# SCH_shield_test_2024-01-13.net
KiCad netlist of a schematic drawn in EasyEDA
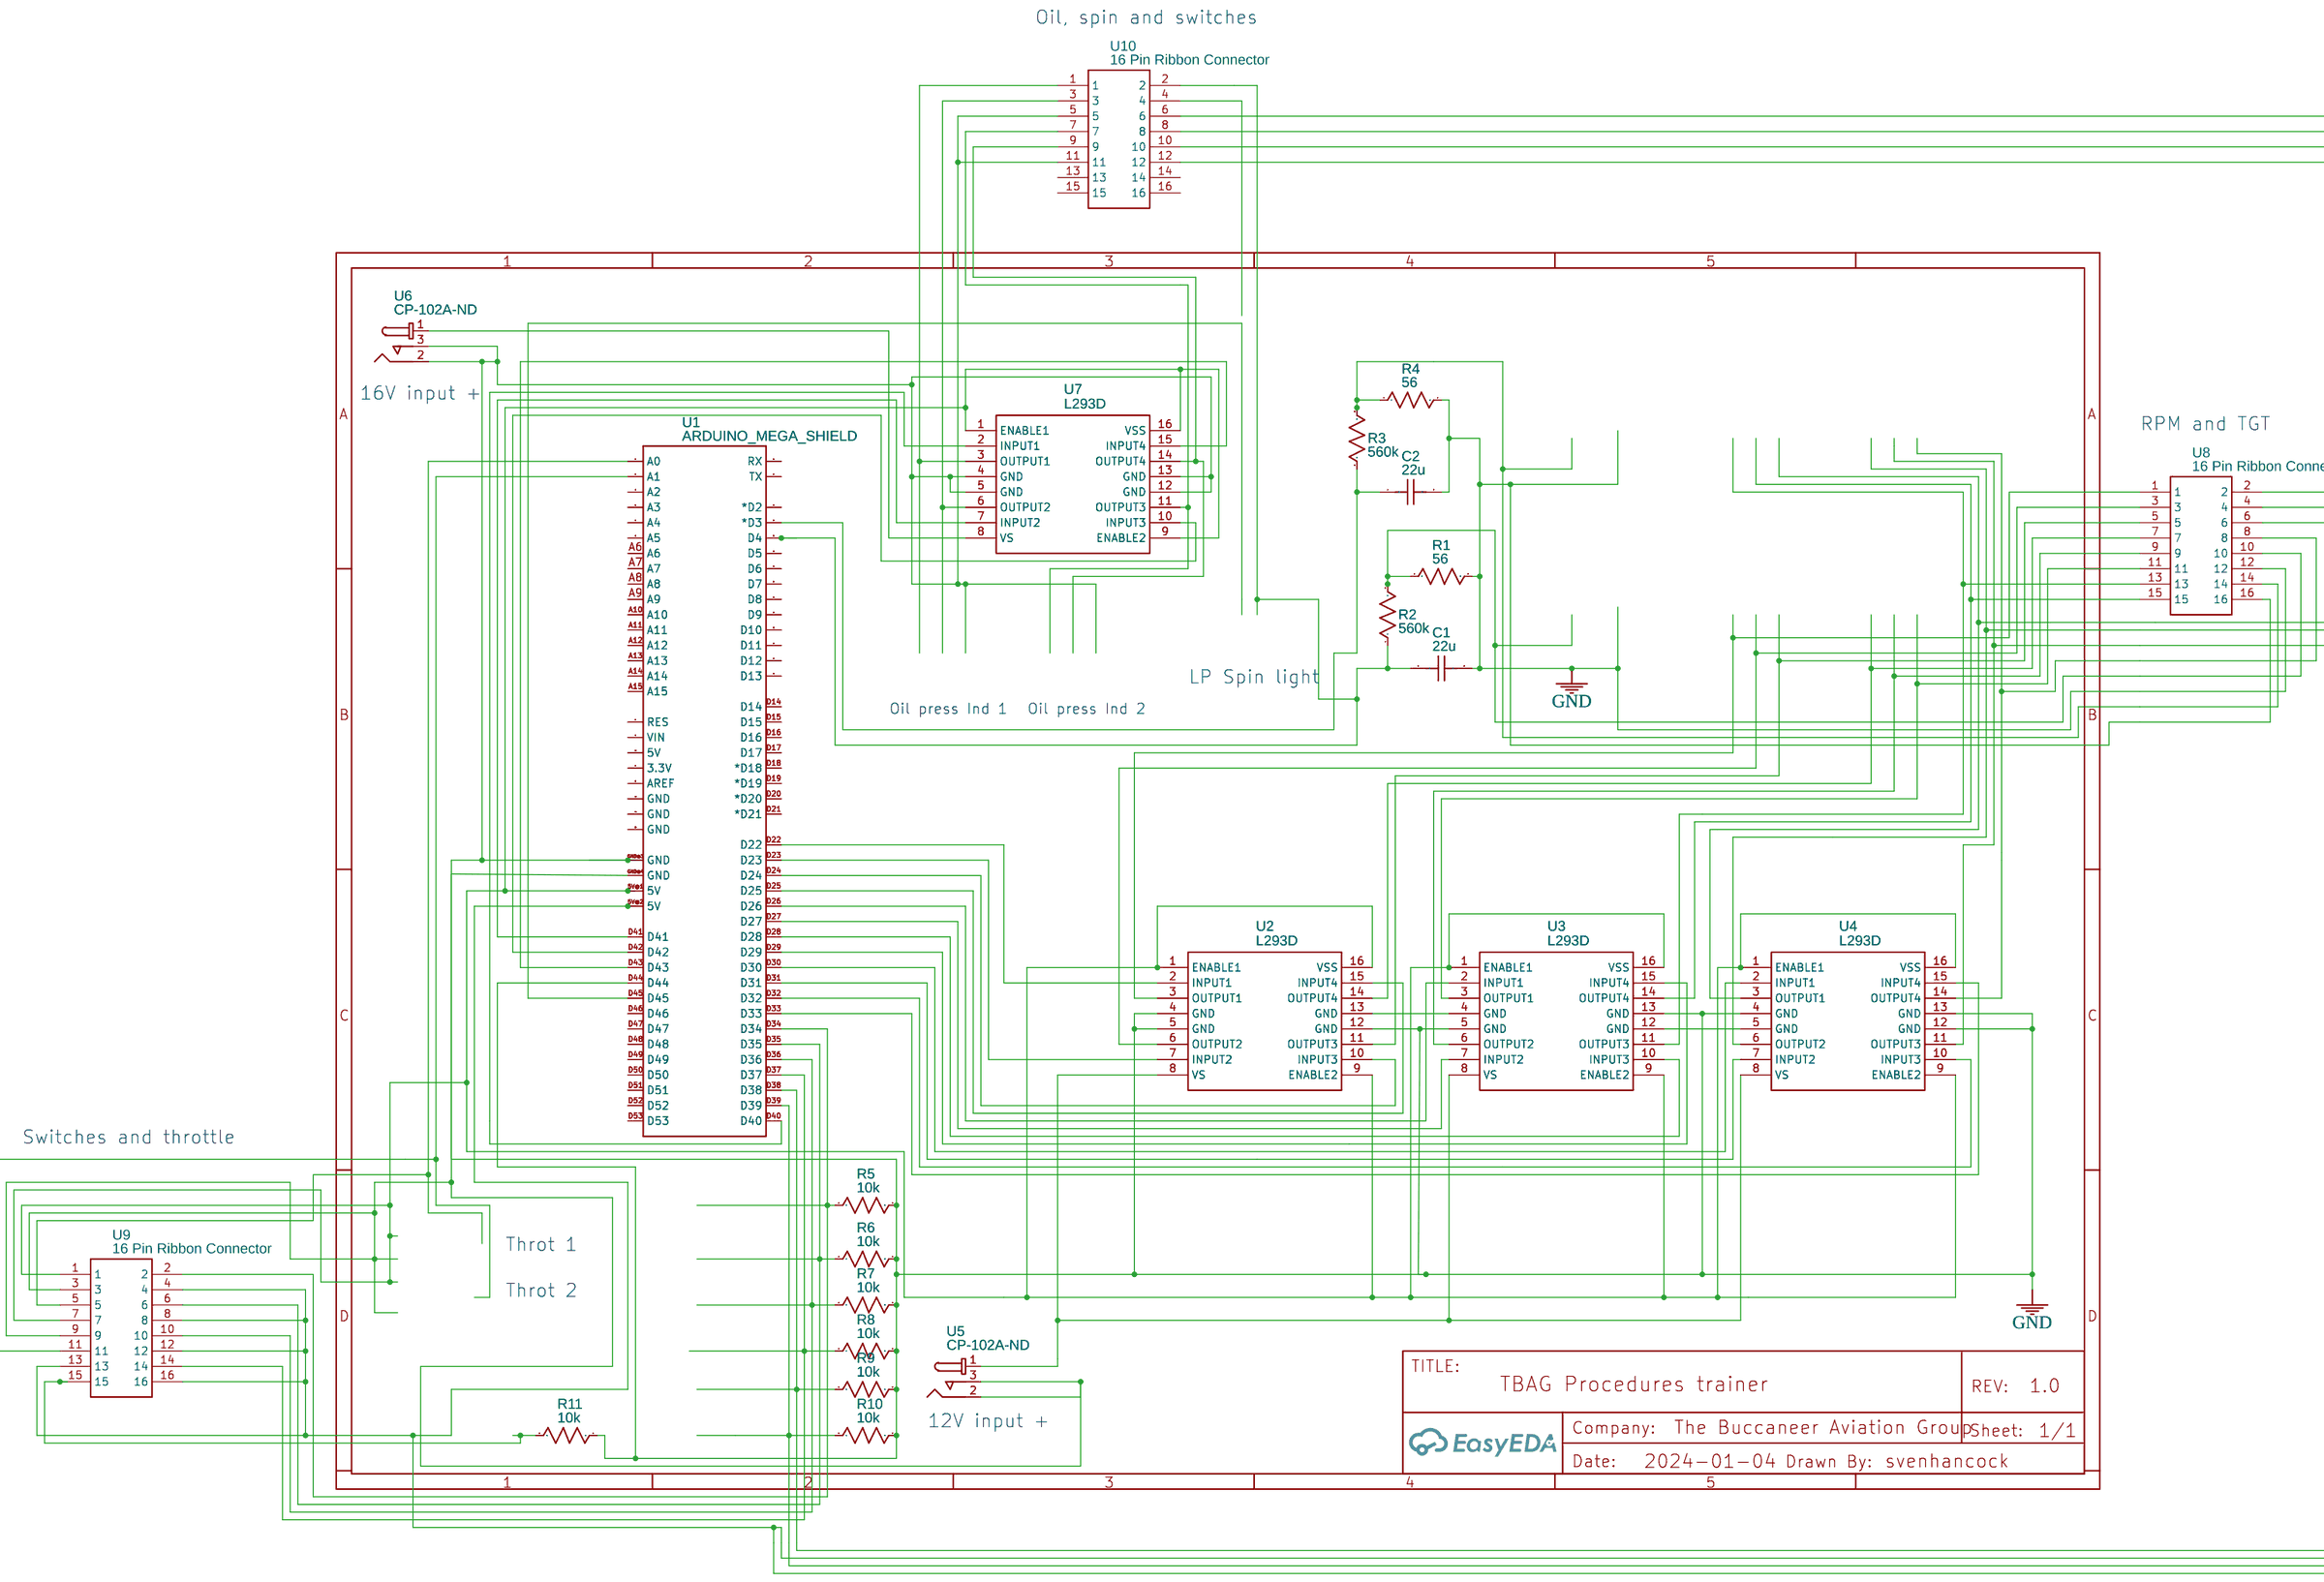
[diagram p0: schematic sheet]

(export (version "E")
  (design (tool "Eeschema 10.0.6"))
  (components
    (comp (ref "C1") (value "22u") (libsource (lib "") (part "C_0603_US")))
    (comp (ref "C2") (value "22u") (libsource (lib "") (part "C_0603_US")))
    (comp (ref "R1") (value "56") (libsource (lib "") (part "R_0603_US")))
    (comp (ref "R2") (value "560k") (libsource (lib "") (part "R_0603_US_1")))
    (comp (ref "R3") (value "560k") (libsource (lib "") (part "R_0603_US_1")))
    (comp (ref "R4") (value "56") (libsource (lib "") (part "R_0603_US")))
    (comp (ref "R5") (value "10k") (libsource (lib "") (part "R_0603_US")))
    (comp (ref "R6") (value "10k") (libsource (lib "") (part "R_0603_US")))
    (comp (ref "R7") (value "10k") (libsource (lib "") (part "R_0603_US")))
    (comp (ref "R8") (value "10k") (libsource (lib "") (part "R_0603_US")))
    (comp (ref "R9") (value "10k") (libsource (lib "") (part "R_0603_US")))
    (comp (ref "R10") (value "10k") (libsource (lib "") (part "R_0603_US")))
    (comp (ref "R11") (value "10k") (libsource (lib "") (part "R_0603_US")))
    (comp (ref "U1") (value "ARDUINO_MEGA_SHIELD") (libsource (lib "") (part "ARDUINO_MEGA_SHIELD")))
    (comp (ref "U2")
      (value "L293D")
      (fields (field (name "Manufacturer") "ST(意法半导体)"))
      (libsource (lib "") (part "L293D"))
    )
    (comp (ref "U3")
      (value "L293D")
      (fields (field (name "Manufacturer") "ST(意法半导体)"))
      (libsource (lib "") (part "L293D"))
    )
    (comp (ref "U4")
      (value "L293D")
      (fields (field (name "Manufacturer") "ST(意法半导体)"))
      (libsource (lib "") (part "L293D"))
    )
    (comp (ref "U5") (value "CP-102A-ND") (libsource (lib "") (part "CP-102A-ND")))
    (comp (ref "U6") (value "CP-102A-ND") (libsource (lib "") (part "CP-102A-ND")))
    (comp (ref "U7")
      (value "L293D")
      (fields (field (name "Manufacturer") "ST(意法半导体)"))
      (libsource (lib "") (part "L293D"))
    )
    (comp (ref "U8") (value "16 Pin Ribbon Connector") (libsource (lib "") (part "16 Pin Ribbon Connector")))
    (comp (ref "U9") (value "16 Pin Ribbon Connector") (libsource (lib "") (part "16 Pin Ribbon Connector")))
    (comp (ref "U10") (value "16 Pin Ribbon Connector") (libsource (lib "") (part "16 Pin Ribbon Connector")))
  )
  (nets
    (net (code "1") (name "GND") (class "Default")
      (node (ref "C1") (pin "2") (pinfunction "2_2") (pintype "unspecified"))
      (node (ref "C2") (pin "2") (pinfunction "2_2") (pintype "unspecified"))
      (node (ref "R1") (pin "2") (pinfunction "2_2") (pintype "unspecified"))
      (node (ref "R10") (pin "2") (pinfunction "2_2") (pintype "unspecified"))
      (node (ref "R11") (pin "2") (pinfunction "2_2") (pintype "unspecified"))
      (node (ref "R4") (pin "2") (pinfunction "2_2") (pintype "unspecified"))
      (node (ref "R5") (pin "2") (pinfunction "2_2") (pintype "unspecified"))
      (node (ref "R6") (pin "2") (pinfunction "2_2") (pintype "unspecified"))
      (node (ref "R7") (pin "2") (pinfunction "2_2") (pintype "unspecified"))
      (node (ref "R8") (pin "2") (pinfunction "2_2") (pintype "unspecified"))
      (node (ref "R9") (pin "2") (pinfunction "2_2") (pintype "unspecified"))
      (node (ref "U1") (pin "D44") (pinfunction "D44_D44") (pintype "unspecified"))
      (node (ref "U1") (pin "GND@3") (pinfunction "GND_GND@3") (pintype "unspecified"))
      (node (ref "U10") (pin "11") (pinfunction "11_11") (pintype "unspecified"))
      (node (ref "U10") (pin "5") (pinfunction "5_5") (pintype "unspecified"))
      (node (ref "U2") (pin "12") (pinfunction "GND_12") (pintype "unspecified"))
      (node (ref "U2") (pin "4") (pinfunction "GND_4") (pintype "unspecified"))
      (node (ref "U2") (pin "5") (pinfunction "GND_5") (pintype "unspecified"))
      (node (ref "U3") (pin "13") (pinfunction "GND_13") (pintype "unspecified"))
      (node (ref "U3") (pin "5") (pinfunction "GND_5") (pintype "unspecified"))
      (node (ref "U4") (pin "12") (pinfunction "GND_12") (pintype "unspecified"))
      (node (ref "U4") (pin "13") (pinfunction "GND_13") (pintype "unspecified"))
      (node (ref "U4") (pin "4") (pinfunction "GND_4") (pintype "unspecified"))
      (node (ref "U6") (pin "2") (pintype "unspecified"))
      (node (ref "U6") (pin "3") (pintype "unspecified"))
      (node (ref "U7") (pin "12") (pinfunction "GND_12") (pintype "unspecified"))
      (node (ref "U7") (pin "13") (pinfunction "GND_13") (pintype "unspecified"))
      (node (ref "U7") (pin "4") (pinfunction "GND_4") (pintype "unspecified"))
      (node (ref "U7") (pin "5") (pinfunction "GND_5") (pintype "unspecified"))
      (node (ref "U8") (pin "12") (pinfunction "12_12") (pintype "unspecified"))
      (node (ref "U8") (pin "16") (pinfunction "16_16") (pintype "unspecified"))
    )
    (net (code "2") (name "Net-(C1-Pad1)") (class "Default")
      (node (ref "C1") (pin "1") (pinfunction "1_1") (pintype "unspecified"))
      (node (ref "R2") (pin "1") (pinfunction "1_1") (pintype "unspecified"))
      (node (ref "U1") (pin "D4") (pinfunction "D4_D4") (pintype "unspecified"))
      (node (ref "U10") (pin "2") (pinfunction "2_2") (pintype "unspecified"))
    )
    (net (code "3") (name "Net-(R1-Pad1)") (class "Default")
      (node (ref "R1") (pin "1") (pinfunction "1_1") (pintype "unspecified"))
      (node (ref "R2") (pin "2") (pinfunction "2_2") (pintype "unspecified"))
      (node (ref "U8") (pin "10") (pinfunction "10_10") (pintype "unspecified"))
    )
    (net (code "4") (name "Net-(R3-Pad2)") (class "Default")
      (node (ref "R3") (pin "2") (pinfunction "2_2") (pintype "unspecified"))
      (node (ref "R4") (pin "1") (pinfunction "1_1") (pintype "unspecified"))
      (node (ref "U8") (pin "14") (pinfunction "14_14") (pintype "unspecified"))
    )
    (net (code "5") (name "Net-(R5-Pad1)") (class "Default")
      (node (ref "R5") (pin "1") (pinfunction "1_1") (pintype "unspecified"))
      (node (ref "U1") (pin "D34") (pinfunction "D34_D34") (pintype "unspecified"))
      (node (ref "U9") (pin "2") (pinfunction "2_2") (pintype "unspecified"))
    )
    (net (code "6") (name "Net-(R6-Pad1)") (class "Default")
      (node (ref "R6") (pin "1") (pinfunction "1_1") (pintype "unspecified"))
      (node (ref "U1") (pin "D35") (pinfunction "D35_D35") (pintype "unspecified"))
      (node (ref "U9") (pin "6") (pinfunction "6_6") (pintype "unspecified"))
    )
    (net (code "7") (name "Net-(R7-Pad1)") (class "Default")
      (node (ref "R7") (pin "1") (pinfunction "1_1") (pintype "unspecified"))
      (node (ref "U1") (pin "D36") (pinfunction "D36_D36") (pintype "unspecified"))
      (node (ref "U9") (pin "10") (pinfunction "10_10") (pintype "unspecified"))
    )
    (net (code "8") (name "Net-(R8-Pad1)") (class "Default")
      (node (ref "R8") (pin "1") (pinfunction "1_1") (pintype "unspecified"))
      (node (ref "U1") (pin "D37") (pinfunction "D37_D37") (pintype "unspecified"))
      (node (ref "U9") (pin "14") (pinfunction "14_14") (pintype "unspecified"))
    )
    (net (code "9") (name "Net-(R9-Pad1)") (class "Default")
      (node (ref "R9") (pin "1") (pinfunction "1_1") (pintype "unspecified"))
      (node (ref "U1") (pin "D38") (pinfunction "D38_D38") (pintype "unspecified"))
      (node (ref "U10") (pin "6") (pinfunction "6_6") (pintype "unspecified"))
    )
    (net (code "10") (name "Net-(R10-Pad1)") (class "Default")
      (node (ref "R10") (pin "1") (pinfunction "1_1") (pintype "unspecified"))
      (node (ref "U1") (pin "D39") (pinfunction "D39_D39") (pintype "unspecified"))
      (node (ref "U10") (pin "10") (pinfunction "10_10") (pintype "unspecified"))
    )
    (net (code "11") (name "Net-(R11-Pad1)") (class "Default")
      (node (ref "R11") (pin "1") (pinfunction "1_1") (pintype "unspecified"))
      (node (ref "U9") (pin "15") (pinfunction "15_15") (pintype "unspecified"))
    )
    (net (code "12") (name "Net-(U1-*D3)") (class "Default")
      (node (ref "C2") (pin "1") (pinfunction "1_1") (pintype "unspecified"))
      (node (ref "R3") (pin "1") (pinfunction "1_1") (pintype "unspecified"))
      (node (ref "U1") (pin "D3") (pinfunction "*D3_D3") (pintype "unspecified"))
    )
    (net (code "13") (name "Net-(U1-5V-Pad5V@2)") (class "Default")
      (node (ref "U1") (pin "5V@2") (pinfunction "5V_5V@2") (pintype "unspecified"))
      (node (ref "U10") (pin "12") (pinfunction "12_12") (pintype "unspecified"))
      (node (ref "U10") (pin "8") (pinfunction "8_8") (pintype "unspecified"))
      (node (ref "U9") (pin "12") (pinfunction "12_12") (pintype "unspecified"))
      (node (ref "U9") (pin "13") (pinfunction "13_13") (pintype "unspecified"))
      (node (ref "U9") (pin "16") (pinfunction "16_16") (pintype "unspecified"))
      (node (ref "U9") (pin "4") (pinfunction "4_4") (pintype "unspecified"))
      (node (ref "U9") (pin "8") (pinfunction "8_8") (pintype "unspecified"))
    )
    (net (code "14") (name "Net-(U1-PadA0)") (class "Default")
      (node (ref "U1") (pin "A0") (pinfunction "A0_A0") (pintype "unspecified"))
      (node (ref "U9") (pin "5") (pinfunction "5_5") (pintype "unspecified"))
    )
    (net (code "15") (name "Net-(U1-PadA1)") (class "Default")
      (node (ref "U1") (pin "A1") (pinfunction "A1_A1") (pintype "unspecified"))
      (node (ref "U9") (pin "11") (pinfunction "11_11") (pintype "unspecified"))
    )
    (net (code "16") (name "Net-(U2-ENABLE1)") (class "Default")
      (node (ref "U1") (pin "5V@1") (pinfunction "5V_5V@1") (pintype "unspecified"))
      (node (ref "U2") (pin "1") (pinfunction "ENABLE1_1") (pintype "unspecified"))
      (node (ref "U2") (pin "16") (pinfunction "VSS_16") (pintype "unspecified"))
      (node (ref "U2") (pin "9") (pinfunction "ENABLE2_9") (pintype "unspecified"))
      (node (ref "U3") (pin "1") (pinfunction "ENABLE1_1") (pintype "unspecified"))
      (node (ref "U3") (pin "16") (pinfunction "VSS_16") (pintype "unspecified"))
      (node (ref "U3") (pin "9") (pinfunction "ENABLE2_9") (pintype "unspecified"))
      (node (ref "U4") (pin "1") (pinfunction "ENABLE1_1") (pintype "unspecified"))
      (node (ref "U4") (pin "16") (pinfunction "VSS_16") (pintype "unspecified"))
      (node (ref "U4") (pin "9") (pinfunction "ENABLE2_9") (pintype "unspecified"))
      (node (ref "U7") (pin "1") (pinfunction "ENABLE1_1") (pintype "unspecified"))
      (node (ref "U7") (pin "16") (pinfunction "VSS_16") (pintype "unspecified"))
      (node (ref "U7") (pin "9") (pinfunction "ENABLE2_9") (pintype "unspecified"))
      (node (ref "U9") (pin "1") (pinfunction "1_1") (pintype "unspecified"))
      (node (ref "U9") (pin "7") (pinfunction "7_7") (pintype "unspecified"))
    )
    (net (code "17") (name "Net-(U2-GND-Pad13)") (class "Default")
      (node (ref "U2") (pin "13") (pinfunction "GND_13") (pintype "unspecified"))
      (node (ref "U3") (pin "4") (pinfunction "GND_4") (pintype "unspecified"))
    )
    (net (code "18") (name "Net-(U2-INPUT1)") (class "Default")
      (node (ref "U1") (pin "D22") (pinfunction "D22_D22") (pintype "unspecified"))
      (node (ref "U2") (pin "2") (pinfunction "INPUT1_2") (pintype "unspecified"))
    )
    (net (code "19") (name "Net-(U2-INPUT2)") (class "Default")
      (node (ref "U1") (pin "D23") (pinfunction "D23_D23") (pintype "unspecified"))
      (node (ref "U2") (pin "7") (pinfunction "INPUT2_7") (pintype "unspecified"))
    )
    (net (code "20") (name "Net-(U2-INPUT3)") (class "Default")
      (node (ref "U1") (pin "D24") (pinfunction "D24_D24") (pintype "unspecified"))
      (node (ref "U2") (pin "10") (pinfunction "INPUT3_10") (pintype "unspecified"))
    )
    (net (code "21") (name "Net-(U2-INPUT4)") (class "Default")
      (node (ref "U1") (pin "D25") (pinfunction "D25_D25") (pintype "unspecified"))
      (node (ref "U2") (pin "15") (pinfunction "INPUT4_15") (pintype "unspecified"))
    )
    (net (code "22") (name "Net-(U2-OUTPUT1)") (class "Default")
      (node (ref "U2") (pin "3") (pinfunction "OUTPUT1_3") (pintype "unspecified"))
      (node (ref "U8") (pin "1") (pinfunction "1_1") (pintype "unspecified"))
    )
    (net (code "23") (name "Net-(U2-OUTPUT2)") (class "Default")
      (node (ref "U2") (pin "6") (pinfunction "OUTPUT2_6") (pintype "unspecified"))
      (node (ref "U8") (pin "3") (pinfunction "3_3") (pintype "unspecified"))
    )
    (net (code "24") (name "Net-(U2-OUTPUT3)") (class "Default")
      (node (ref "U2") (pin "11") (pinfunction "OUTPUT3_11") (pintype "unspecified"))
      (node (ref "U8") (pin "5") (pinfunction "5_5") (pintype "unspecified"))
    )
    (net (code "25") (name "Net-(U2-OUTPUT4)") (class "Default")
      (node (ref "U2") (pin "14") (pinfunction "OUTPUT4_14") (pintype "unspecified"))
      (node (ref "U8") (pin "7") (pinfunction "7_7") (pintype "unspecified"))
    )
    (net (code "26") (name "Net-(U2-VS)") (class "Default")
      (node (ref "U2") (pin "8") (pinfunction "VS_8") (pintype "unspecified"))
      (node (ref "U3") (pin "8") (pinfunction "VS_8") (pintype "unspecified"))
      (node (ref "U4") (pin "8") (pinfunction "VS_8") (pintype "unspecified"))
      (node (ref "U5") (pin "1") (pintype "unspecified"))
    )
    (net (code "27") (name "Net-(U3-GND-Pad12)") (class "Default")
      (node (ref "U3") (pin "12") (pinfunction "GND_12") (pintype "unspecified"))
      (node (ref "U4") (pin "5") (pinfunction "GND_5") (pintype "unspecified"))
    )
    (net (code "28") (name "Net-(U3-INPUT1)") (class "Default")
      (node (ref "U1") (pin "D26") (pinfunction "D26_D26") (pintype "unspecified"))
      (node (ref "U3") (pin "2") (pinfunction "INPUT1_2") (pintype "unspecified"))
    )
    (net (code "29") (name "Net-(U3-INPUT2)") (class "Default")
      (node (ref "U1") (pin "D27") (pinfunction "D27_D27") (pintype "unspecified"))
      (node (ref "U3") (pin "7") (pinfunction "INPUT2_7") (pintype "unspecified"))
    )
    (net (code "30") (name "Net-(U3-INPUT3)") (class "Default")
      (node (ref "U1") (pin "D28") (pinfunction "D28_D28") (pintype "unspecified"))
      (node (ref "U3") (pin "10") (pinfunction "INPUT3_10") (pintype "unspecified"))
    )
    (net (code "31") (name "Net-(U3-INPUT4)") (class "Default")
      (node (ref "U1") (pin "D29") (pinfunction "D29_D29") (pintype "unspecified"))
      (node (ref "U3") (pin "15") (pinfunction "INPUT4_15") (pintype "unspecified"))
    )
    (net (code "32") (name "Net-(U3-OUTPUT1)") (class "Default")
      (node (ref "U3") (pin "3") (pinfunction "OUTPUT1_3") (pintype "unspecified"))
      (node (ref "U8") (pin "11") (pinfunction "11_11") (pintype "unspecified"))
    )
    (net (code "33") (name "Net-(U3-OUTPUT2)") (class "Default")
      (node (ref "U3") (pin "6") (pinfunction "OUTPUT2_6") (pintype "unspecified"))
      (node (ref "U8") (pin "9") (pinfunction "9_9") (pintype "unspecified"))
    )
    (net (code "34") (name "Net-(U3-OUTPUT3)") (class "Default")
      (node (ref "U3") (pin "11") (pinfunction "OUTPUT3_11") (pintype "unspecified"))
      (node (ref "U8") (pin "13") (pinfunction "13_13") (pintype "unspecified"))
    )
    (net (code "35") (name "Net-(U3-OUTPUT4)") (class "Default")
      (node (ref "U3") (pin "14") (pinfunction "OUTPUT4_14") (pintype "unspecified"))
      (node (ref "U8") (pin "15") (pinfunction "15_15") (pintype "unspecified"))
    )
    (net (code "36") (name "Net-(U4-INPUT1)") (class "Default")
      (node (ref "U1") (pin "D30") (pinfunction "D30_D30") (pintype "unspecified"))
      (node (ref "U4") (pin "2") (pinfunction "INPUT1_2") (pintype "unspecified"))
    )
    (net (code "37") (name "Net-(U4-INPUT2)") (class "Default")
      (node (ref "U1") (pin "D31") (pinfunction "D31_D31") (pintype "unspecified"))
      (node (ref "U4") (pin "7") (pinfunction "INPUT2_7") (pintype "unspecified"))
    )
    (net (code "38") (name "Net-(U4-INPUT3)") (class "Default")
      (node (ref "U1") (pin "D32") (pinfunction "D32_D32") (pintype "unspecified"))
      (node (ref "U4") (pin "10") (pinfunction "INPUT3_10") (pintype "unspecified"))
    )
    (net (code "39") (name "Net-(U4-INPUT4)") (class "Default")
      (node (ref "U1") (pin "D33") (pinfunction "D33_D33") (pintype "unspecified"))
      (node (ref "U4") (pin "15") (pinfunction "INPUT4_15") (pintype "unspecified"))
    )
    (net (code "40") (name "Net-(U4-OUTPUT1)") (class "Default")
      (node (ref "U4") (pin "3") (pinfunction "OUTPUT1_3") (pintype "unspecified"))
      (node (ref "U8") (pin "2") (pinfunction "2_2") (pintype "unspecified"))
    )
    (net (code "41") (name "Net-(U4-OUTPUT2)") (class "Default")
      (node (ref "U4") (pin "6") (pinfunction "OUTPUT2_6") (pintype "unspecified"))
      (node (ref "U8") (pin "4") (pinfunction "4_4") (pintype "unspecified"))
    )
    (net (code "42") (name "Net-(U4-OUTPUT3)") (class "Default")
      (node (ref "U4") (pin "11") (pinfunction "OUTPUT3_11") (pintype "unspecified"))
      (node (ref "U8") (pin "6") (pinfunction "6_6") (pintype "unspecified"))
    )
    (net (code "43") (name "Net-(U4-OUTPUT4)") (class "Default")
      (node (ref "U4") (pin "14") (pinfunction "OUTPUT4_14") (pintype "unspecified"))
      (node (ref "U8") (pin "8") (pinfunction "8_8") (pintype "unspecified"))
    )
    (net (code "44") (name "Net-(U5-Pad2)") (class "Default")
      (node (ref "U5") (pin "2") (pintype "unspecified"))
      (node (ref "U5") (pin "3") (pintype "unspecified"))
      (node (ref "U9") (pin "3") (pinfunction "3_3") (pintype "unspecified"))
      (node (ref "U9") (pin "9") (pinfunction "9_9") (pintype "unspecified"))
    )
    (net (code "45") (name "Net-(U7-INPUT1)") (class "Default")
      (node (ref "U1") (pin "D40") (pinfunction "D40_D40") (pintype "unspecified"))
      (node (ref "U7") (pin "2") (pinfunction "INPUT1_2") (pintype "unspecified"))
    )
    (net (code "46") (name "Net-(U7-INPUT2)") (class "Default")
      (node (ref "U1") (pin "D41") (pinfunction "D41_D41") (pintype "unspecified"))
      (node (ref "U7") (pin "7") (pinfunction "INPUT2_7") (pintype "unspecified"))
    )
    (net (code "47") (name "Net-(U7-INPUT3)") (class "Default")
      (node (ref "U1") (pin "D42") (pinfunction "D42_D42") (pintype "unspecified"))
      (node (ref "U7") (pin "10") (pinfunction "INPUT3_10") (pintype "unspecified"))
    )
    (net (code "48") (name "Net-(U7-INPUT4)") (class "Default")
      (node (ref "U1") (pin "D43") (pinfunction "D43_D43") (pintype "unspecified"))
      (node (ref "U7") (pin "15") (pinfunction "INPUT4_15") (pintype "unspecified"))
    )
    (net (code "49") (name "Net-(U7-OUTPUT1)") (class "Default")
      (node (ref "U10") (pin "1") (pinfunction "1_1") (pintype "unspecified"))
      (node (ref "U7") (pin "3") (pinfunction "OUTPUT1_3") (pintype "unspecified"))
    )
    (net (code "50") (name "Net-(U7-OUTPUT2)") (class "Default")
      (node (ref "U10") (pin "3") (pinfunction "3_3") (pintype "unspecified"))
      (node (ref "U7") (pin "6") (pinfunction "OUTPUT2_6") (pintype "unspecified"))
    )
    (net (code "51") (name "Net-(U7-OUTPUT3)") (class "Default")
      (node (ref "U10") (pin "7") (pinfunction "7_7") (pintype "unspecified"))
      (node (ref "U7") (pin "11") (pinfunction "OUTPUT3_11") (pintype "unspecified"))
    )
    (net (code "52") (name "Net-(U7-OUTPUT4)") (class "Default")
      (node (ref "U10") (pin "9") (pinfunction "9_9") (pintype "unspecified"))
      (node (ref "U7") (pin "14") (pinfunction "OUTPUT4_14") (pintype "unspecified"))
    )
    (net (code "53") (name "Net-(U7-VS)") (class "Default")
      (node (ref "U6") (pin "1") (pintype "unspecified"))
      (node (ref "U7") (pin "8") (pinfunction "VS_8") (pintype "unspecified"))
    )
    (net (code "54") (name "unconnected-(U1-*D2-PadD2)") (class "Default")
      (node (ref "U1") (pin "D2") (pinfunction "*D2_D2") (pintype "unspecified"))
    )
    (net (code "55") (name "unconnected-(U1-*D18-PadD18)") (class "Default")
      (node (ref "U1") (pin "D18") (pinfunction "*D18_D18") (pintype "unspecified"))
    )
    (net (code "56") (name "unconnected-(U1-*D19-PadD19)") (class "Default")
      (node (ref "U1") (pin "D19") (pinfunction "*D19_D19") (pintype "unspecified"))
    )
    (net (code "57") (name "unconnected-(U1-*D20-PadD20)") (class "Default")
      (node (ref "U1") (pin "D20") (pinfunction "*D20_D20") (pintype "unspecified"))
    )
    (net (code "58") (name "unconnected-(U1-*D21-PadD21)") (class "Default")
      (node (ref "U1") (pin "D21") (pinfunction "*D21_D21") (pintype "unspecified"))
    )
    (net (code "59") (name "unconnected-(U1-5V-Pad5V@0)") (class "Default")
      (node (ref "U1") (pin "5V@0") (pinfunction "5V_5V@0") (pintype "passive"))
    )
    (net (code "60") (name "unconnected-(U1-GND-PadGND@0)") (class "Default")
      (node (ref "U1") (pin "GND@0") (pinfunction "GND_GND@0") (pintype "unspecified"))
    )
    (net (code "61") (name "unconnected-(U1-GND-PadGND@1)") (class "Default")
      (node (ref "U1") (pin "GND@1") (pinfunction "GND_GND@1") (pintype "unspecified"))
    )
    (net (code "62") (name "unconnected-(U1-GND-PadGND@2)") (class "Default")
      (node (ref "U1") (pin "GND@2") (pinfunction "GND_GND@2") (pintype "unspecified"))
    )
    (net (code "63") (name "unconnected-(U1-GND-PadGND@4)") (class "Default")
      (node (ref "U1") (pin "GND@4") (pinfunction "GND_GND@4") (pintype "unspecified"))
    )
    (net (code "64") (name "unconnected-(U1-Pad3.3V)") (class "Default")
      (node (ref "U1") (pin "3.3V") (pinfunction "3.3V_3.3V") (pintype "unspecified"))
    )
    (net (code "65") (name "unconnected-(U1-PadA2)") (class "Default")
      (node (ref "U1") (pin "A2") (pinfunction "A2_A2") (pintype "unspecified"))
    )
    (net (code "66") (name "unconnected-(U1-PadA3)") (class "Default")
      (node (ref "U1") (pin "A3") (pinfunction "A3_A3") (pintype "unspecified"))
    )
    (net (code "67") (name "unconnected-(U1-PadA4)") (class "Default")
      (node (ref "U1") (pin "A4") (pinfunction "A4_A4") (pintype "unspecified"))
    )
    (net (code "68") (name "unconnected-(U1-PadA5)") (class "Default")
      (node (ref "U1") (pin "A5") (pinfunction "A5_A5") (pintype "unspecified"))
    )
    (net (code "69") (name "unconnected-(U1-PadA6)") (class "Default")
      (node (ref "U1") (pin "A6") (pinfunction "A6_A6") (pintype "unspecified"))
    )
    (net (code "70") (name "unconnected-(U1-PadA7)") (class "Default")
      (node (ref "U1") (pin "A7") (pinfunction "A7_A7") (pintype "unspecified"))
    )
    (net (code "71") (name "unconnected-(U1-PadA8)") (class "Default")
      (node (ref "U1") (pin "A8") (pinfunction "A8_A8") (pintype "unspecified"))
    )
    (net (code "72") (name "unconnected-(U1-PadA9)") (class "Default")
      (node (ref "U1") (pin "A9") (pinfunction "A9_A9") (pintype "unspecified"))
    )
    (net (code "73") (name "unconnected-(U1-PadA10)") (class "Default")
      (node (ref "U1") (pin "A10") (pinfunction "A10_A10") (pintype "unspecified"))
    )
    (net (code "74") (name "unconnected-(U1-PadA11)") (class "Default")
      (node (ref "U1") (pin "A11") (pinfunction "A11_A11") (pintype "unspecified"))
    )
    (net (code "75") (name "unconnected-(U1-PadA12)") (class "Default")
      (node (ref "U1") (pin "A12") (pinfunction "A12_A12") (pintype "unspecified"))
    )
    (net (code "76") (name "unconnected-(U1-PadA13)") (class "Default")
      (node (ref "U1") (pin "A13") (pinfunction "A13_A13") (pintype "unspecified"))
    )
    (net (code "77") (name "unconnected-(U1-PadA14)") (class "Default")
      (node (ref "U1") (pin "A14") (pinfunction "A14_A14") (pintype "unspecified"))
    )
    (net (code "78") (name "unconnected-(U1-PadA15)") (class "Default")
      (node (ref "U1") (pin "A15") (pinfunction "A15_A15") (pintype "unspecified"))
    )
    (net (code "79") (name "unconnected-(U1-PadAREF)") (class "Default")
      (node (ref "U1") (pin "AREF") (pinfunction "AREF_AREF") (pintype "unspecified"))
    )
    (net (code "80") (name "unconnected-(U1-PadD5)") (class "Default")
      (node (ref "U1") (pin "D5") (pinfunction "D5_D5") (pintype "unspecified"))
    )
    (net (code "81") (name "unconnected-(U1-PadD6)") (class "Default")
      (node (ref "U1") (pin "D6") (pinfunction "D6_D6") (pintype "unspecified"))
    )
    (net (code "82") (name "unconnected-(U1-PadD7)") (class "Default")
      (node (ref "U1") (pin "D7") (pinfunction "D7_D7") (pintype "unspecified"))
    )
    (net (code "83") (name "unconnected-(U1-PadD8)") (class "Default")
      (node (ref "U1") (pin "D8") (pinfunction "D8_D8") (pintype "unspecified"))
    )
    (net (code "84") (name "unconnected-(U1-PadD9)") (class "Default")
      (node (ref "U1") (pin "D9") (pinfunction "D9_D9") (pintype "unspecified"))
    )
    (net (code "85") (name "unconnected-(U1-PadD10)") (class "Default")
      (node (ref "U1") (pin "D10") (pinfunction "D10_D10") (pintype "unspecified"))
    )
    (net (code "86") (name "unconnected-(U1-PadD11)") (class "Default")
      (node (ref "U1") (pin "D11") (pinfunction "D11_D11") (pintype "unspecified"))
    )
    (net (code "87") (name "unconnected-(U1-PadD12)") (class "Default")
      (node (ref "U1") (pin "D12") (pinfunction "D12_D12") (pintype "unspecified"))
    )
    (net (code "88") (name "unconnected-(U1-PadD13)") (class "Default")
      (node (ref "U1") (pin "D13") (pinfunction "D13_D13") (pintype "unspecified"))
    )
    (net (code "89") (name "unconnected-(U1-PadD14)") (class "Default")
      (node (ref "U1") (pin "D14") (pinfunction "D14_D14") (pintype "unspecified"))
    )
    (net (code "90") (name "unconnected-(U1-PadD15)") (class "Default")
      (node (ref "U1") (pin "D15") (pinfunction "D15_D15") (pintype "unspecified"))
    )
    (net (code "91") (name "unconnected-(U1-PadD16)") (class "Default")
      (node (ref "U1") (pin "D16") (pinfunction "D16_D16") (pintype "unspecified"))
    )
    (net (code "92") (name "unconnected-(U1-PadD17)") (class "Default")
      (node (ref "U1") (pin "D17") (pinfunction "D17_D17") (pintype "unspecified"))
    )
    (net (code "93") (name "unconnected-(U1-PadD45)") (class "Default")
      (node (ref "U1") (pin "D45") (pinfunction "D45_D45") (pintype "unspecified"))
    )
    (net (code "94") (name "unconnected-(U1-PadD46)") (class "Default")
      (node (ref "U1") (pin "D46") (pinfunction "D46_D46") (pintype "unspecified"))
    )
    (net (code "95") (name "unconnected-(U1-PadD47)") (class "Default")
      (node (ref "U1") (pin "D47") (pinfunction "D47_D47") (pintype "unspecified"))
    )
    (net (code "96") (name "unconnected-(U1-PadD48)") (class "Default")
      (node (ref "U1") (pin "D48") (pinfunction "D48_D48") (pintype "unspecified"))
    )
    (net (code "97") (name "unconnected-(U1-PadD49)") (class "Default")
      (node (ref "U1") (pin "D49") (pinfunction "D49_D49") (pintype "unspecified"))
    )
    (net (code "98") (name "unconnected-(U1-PadD50)") (class "Default")
      (node (ref "U1") (pin "D50") (pinfunction "D50_D50") (pintype "unspecified"))
    )
    (net (code "99") (name "unconnected-(U1-PadD51)") (class "Default")
      (node (ref "U1") (pin "D51") (pinfunction "D51_D51") (pintype "unspecified"))
    )
    (net (code "100") (name "unconnected-(U1-PadD52)") (class "Default")
      (node (ref "U1") (pin "D52") (pinfunction "D52_D52") (pintype "unspecified"))
    )
    (net (code "101") (name "unconnected-(U1-PadD53)") (class "Default")
      (node (ref "U1") (pin "D53") (pinfunction "D53_D53") (pintype "unspecified"))
    )
    (net (code "102") (name "unconnected-(U1-PadRES)") (class "Default")
      (node (ref "U1") (pin "RES") (pinfunction "RES_RES") (pintype "unspecified"))
    )
    (net (code "103") (name "unconnected-(U1-PadRX)") (class "Default")
      (node (ref "U1") (pin "RX") (pinfunction "RX_RX") (pintype "unspecified"))
    )
    (net (code "104") (name "unconnected-(U1-PadTX)") (class "Default")
      (node (ref "U1") (pin "TX") (pinfunction "TX_TX") (pintype "unspecified"))
    )
    (net (code "105") (name "unconnected-(U1-PadVIN)") (class "Default")
      (node (ref "U1") (pin "VIN") (pinfunction "VIN_VIN") (pintype "unspecified"))
    )
    (net (code "106") (name "unconnected-(U10-Pad4)") (class "Default")
      (node (ref "U10") (pin "4") (pinfunction "4_4") (pintype "unspecified"))
    )
    (net (code "107") (name "unconnected-(U10-Pad13)") (class "Default")
      (node (ref "U10") (pin "13") (pinfunction "13_13") (pintype "unspecified"))
    )
    (net (code "108") (name "unconnected-(U10-Pad14)") (class "Default")
      (node (ref "U10") (pin "14") (pinfunction "14_14") (pintype "unspecified"))
    )
    (net (code "109") (name "unconnected-(U10-Pad15)") (class "Default")
      (node (ref "U10") (pin "15") (pinfunction "15_15") (pintype "unspecified"))
    )
    (net (code "110") (name "unconnected-(U10-Pad16)") (class "Default")
      (node (ref "U10") (pin "16") (pinfunction "16_16") (pintype "unspecified"))
    )
  )
)
